# AMP_1_1.net
KiCad netlist of a schematic drawn in EAGLE
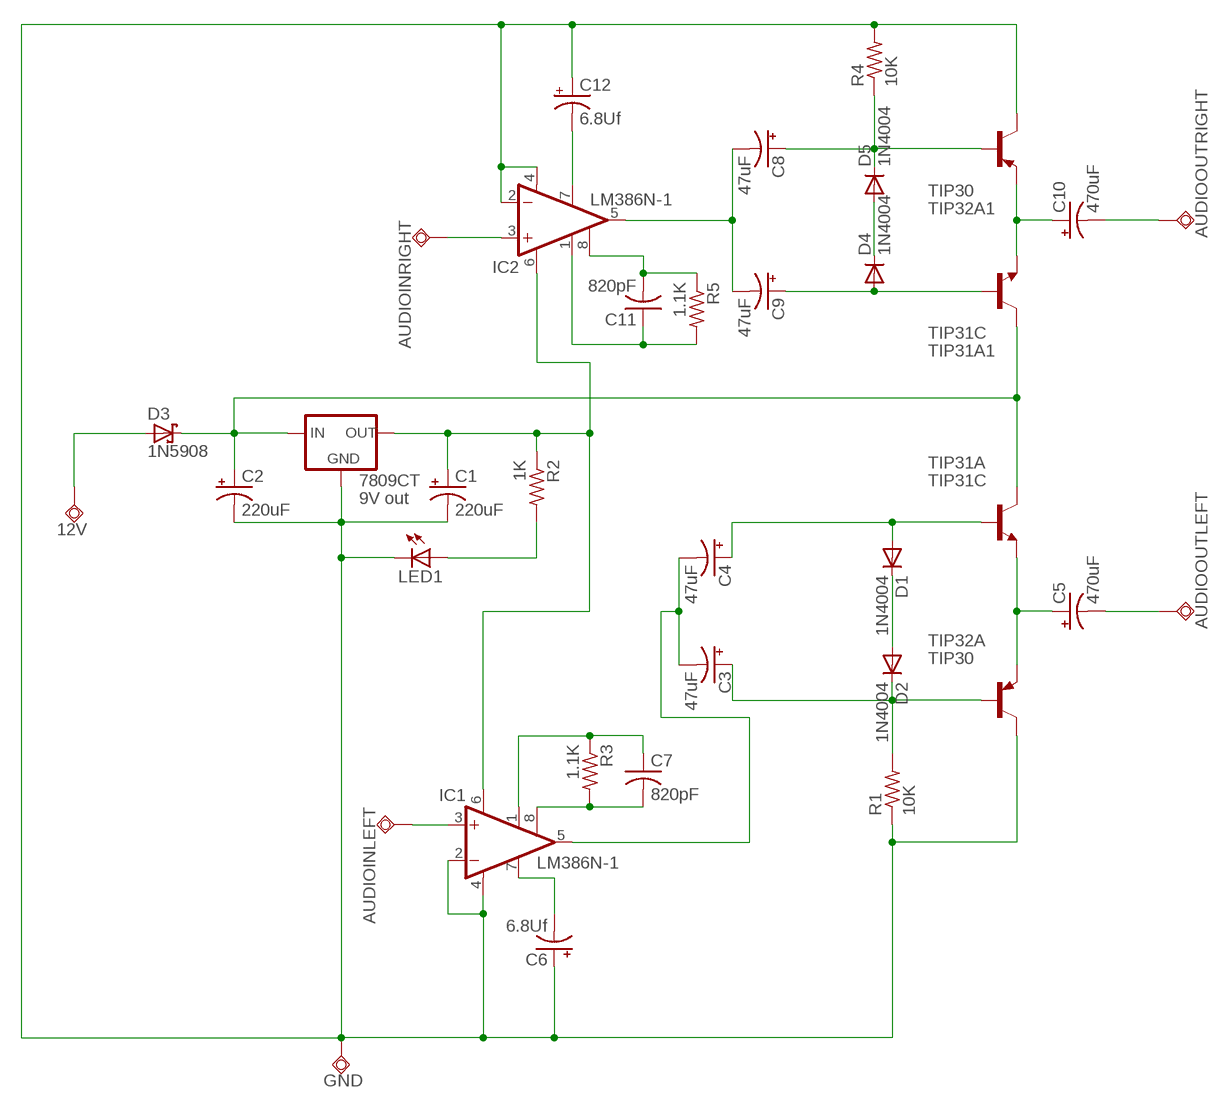
[diagram p0: schematic, sheet 1]

(export (version "E")
  (design (tool "Eeschema 10.0.6"))
  (components
    (comp (ref "12V")
      (value "TPSQPAD1-20")
      (footprint "eagle-import:P1-20")
      (libsource (lib "eagle-import") (part "TPSQPAD1-20"))
    )
    (comp (ref "7809CT")
      (value "9V out")
      (footprint "eagle-import:78XXL")
      (libsource (lib "eagle-import") (part "78XXL"))
    )
    (comp (ref "AUDIOINLEFT")
      (value "TPSQPAD1-20")
      (footprint "eagle-import:P1-20")
      (libsource (lib "eagle-import") (part "TPSQPAD1-20"))
    )
    (comp (ref "AUDIOINRIGHT")
      (value "TPSQPAD1-20")
      (footprint "eagle-import:P1-20")
      (libsource (lib "eagle-import") (part "TPSQPAD1-20"))
    )
    (comp (ref "AUDIOOUTLEFT")
      (value "TPSQPAD1-20")
      (footprint "eagle-import:P1-20")
      (libsource (lib "eagle-import") (part "TPSQPAD1-20"))
    )
    (comp (ref "AUDIOOUTRIGHT")
      (value "TPSQPAD1-20")
      (footprint "eagle-import:P1-20")
      (libsource (lib "eagle-import") (part "TPSQPAD1-20"))
    )
    (comp (ref "C1")
      (value "220uF")
      (footprint "eagle-import:B45181C")
      (libsource (lib "eagle-import") (part "CPOL-USB45181C"))
    )
    (comp (ref "C2")
      (value "220uF")
      (footprint "eagle-import:B45181C")
      (libsource (lib "eagle-import") (part "CPOL-USB45181C"))
    )
    (comp (ref "C3")
      (value "47uF")
      (footprint "eagle-import:E5-4")
      (libsource (lib "eagle-import") (part "CPOL-USE5-4"))
    )
    (comp (ref "C4")
      (value "47uF")
      (footprint "eagle-import:E5-4")
      (libsource (lib "eagle-import") (part "CPOL-USE5-4"))
    )
    (comp (ref "C5")
      (value "470uF")
      (footprint "eagle-import:E5-4")
      (libsource (lib "eagle-import") (part "CPOL-USE5-4"))
    )
    (comp (ref "C6")
      (value "6.8Uf")
      (footprint "eagle-import:E5-4")
      (libsource (lib "eagle-import") (part "CPOL-USE5-4"))
    )
    (comp (ref "C7")
      (value "820pF")
      (footprint "eagle-import:C050-050X075")
      (libsource (lib "eagle-import") (part "C-US050-050X075"))
    )
    (comp (ref "C8")
      (value "47uF")
      (footprint "eagle-import:E5-4")
      (libsource (lib "eagle-import") (part "CPOL-USE5-4"))
    )
    (comp (ref "C9")
      (value "47uF")
      (footprint "eagle-import:E5-4")
      (libsource (lib "eagle-import") (part "CPOL-USE5-4"))
    )
    (comp (ref "C10")
      (value "470uF")
      (footprint "eagle-import:E5-4")
      (libsource (lib "eagle-import") (part "CPOL-USE5-4"))
    )
    (comp (ref "C11")
      (value "820pF")
      (footprint "eagle-import:C050-050X075")
      (libsource (lib "eagle-import") (part "C-US050-050X075"))
    )
    (comp (ref "C12")
      (value "6.8Uf")
      (footprint "eagle-import:E5-4")
      (libsource (lib "eagle-import") (part "CPOL-USE5-4"))
    )
    (comp (ref "D1")
      (value "1N4004")
      (footprint "eagle-import:DO41-10")
      (libsource (lib "eagle-import") (part "1N4004"))
    )
    (comp (ref "D2")
      (value "1N4004")
      (footprint "eagle-import:DO41-10")
      (libsource (lib "eagle-import") (part "1N4004"))
    )
    (comp (ref "D3")
      (value "1N5908")
      (footprint "eagle-import:C4111-15")
      (libsource (lib "eagle-import") (part "1N5908"))
    )
    (comp (ref "D4")
      (value "1N4004")
      (footprint "eagle-import:DO41-10")
      (libsource (lib "eagle-import") (part "1N4004"))
    )
    (comp (ref "D5")
      (value "1N4004")
      (footprint "eagle-import:DO41-10")
      (libsource (lib "eagle-import") (part "1N4004"))
    )
    (comp (ref "GND")
      (value "TPSQPAD1-20")
      (footprint "eagle-import:P1-20")
      (libsource (lib "eagle-import") (part "TPSQPAD1-20"))
    )
    (comp (ref "IC1")
      (value "LM386N-1")
      (footprint "eagle-import:DIL08")
      (libsource (lib "eagle-import") (part "LM386?-N1"))
    )
    (comp (ref "IC2")
      (value "LM386N-1")
      (footprint "eagle-import:DIL08")
      (libsource (lib "eagle-import") (part "LM386?-N1"))
    )
    (comp (ref "LED1")
      (value "LED5MM")
      (footprint "eagle-import:LED5MM")
      (libsource (lib "eagle-import") (part "LED5MM"))
    )
    (comp (ref "R1")
      (value "10K")
      (footprint "eagle-import:0204_7")
      (libsource (lib "eagle-import") (part "R-US_0204/7"))
    )
    (comp (ref "R2")
      (value "1K")
      (footprint "eagle-import:0204_7")
      (libsource (lib "eagle-import") (part "R-US_0204/7"))
    )
    (comp (ref "R3")
      (value "1.1K")
      (footprint "eagle-import:0204_7")
      (libsource (lib "eagle-import") (part "R-US_0204/7"))
    )
    (comp (ref "R4")
      (value "10K")
      (footprint "eagle-import:0204_7")
      (libsource (lib "eagle-import") (part "R-US_0204/7"))
    )
    (comp (ref "R5")
      (value "1.1K")
      (footprint "eagle-import:0204_7")
      (libsource (lib "eagle-import") (part "R-US_0204/7"))
    )
    (comp (ref "TIP31A")
      (value "TIP31C")
      (footprint "eagle-import:TO220")
      (libsource (lib "eagle-import") (part "TIP31C"))
    )
    (comp (ref "TIP31A1")
      (value "TIP31C")
      (footprint "eagle-import:TO220")
      (libsource (lib "eagle-import") (part "TIP31C"))
    )
    (comp (ref "TIP32A")
      (value "TIP30")
      (footprint "eagle-import:TO220")
      (libsource (lib "eagle-import") (part "TIP30"))
    )
    (comp (ref "TIP32A1")
      (value "TIP30")
      (footprint "eagle-import:TO220")
      (libsource (lib "eagle-import") (part "TIP30"))
    )
  )
  (nets
    (net (code "1") (name "Net-(12V-PadTP)") (class "Default")
      (node (ref "12V") (pin "TP") (pinfunction "TP_TP") (pintype "input"))
      (node (ref "D3") (pin "A") (pinfunction "A_A") (pintype "passive"))
    )
    (net (code "2") (name "Net-(AUDIOOUTLEFT-PadTP)") (class "Default")
      (node (ref "AUDIOOUTLEFT") (pin "TP") (pinfunction "TP_TP") (pintype "input"))
      (node (ref "C5") (pin "-") (pinfunction "-_-") (pintype "passive"))
    )
    (net (code "3") (name "Net-(AUDIOOUTRIGHT-PadTP)") (class "Default")
      (node (ref "AUDIOOUTRIGHT") (pin "TP") (pinfunction "TP_TP") (pintype "input"))
      (node (ref "C10") (pin "-") (pinfunction "-_-") (pintype "passive"))
    )
    (net (code "4") (name "Net-(C7-Pad1)") (class "Default")
      (node (ref "C7") (pin "1") (pinfunction "1_1") (pintype "passive"))
      (node (ref "IC1") (pin "1") (pinfunction "GAIN_1") (pintype "passive"))
      (node (ref "R3") (pin "1") (pinfunction "1_1") (pintype "passive"))
    )
    (net (code "5") (name "Net-(C7-Pad2)") (class "Default")
      (node (ref "C7") (pin "2") (pinfunction "2_2") (pintype "passive"))
      (node (ref "IC1") (pin "8") (pinfunction "GAIN_8") (pintype "passive"))
      (node (ref "R3") (pin "2") (pinfunction "2_2") (pintype "passive"))
    )
    (net (code "6") (name "Net-(C11-Pad1)") (class "Default")
      (node (ref "C11") (pin "1") (pinfunction "1_1") (pintype "passive"))
      (node (ref "IC2") (pin "1") (pinfunction "GAIN_1") (pintype "passive"))
      (node (ref "R5") (pin "2") (pinfunction "2_2") (pintype "passive"))
    )
    (net (code "7") (name "Net-(C11-Pad2)") (class "Default")
      (node (ref "C11") (pin "2") (pinfunction "2_2") (pintype "passive"))
      (node (ref "IC2") (pin "8") (pinfunction "GAIN_8") (pintype "passive"))
      (node (ref "R5") (pin "1") (pinfunction "1_1") (pintype "passive"))
    )
    (net (code "8") (name "Net-(D1-PadC)") (class "Default")
      (node (ref "D1") (pin "C") (pinfunction "C_C") (pintype "passive"))
      (node (ref "D2") (pin "A") (pinfunction "A_A") (pintype "passive"))
    )
    (net (code "9") (name "Net-(D4-PadC)") (class "Default")
      (node (ref "D4") (pin "C") (pinfunction "C_C") (pintype "passive"))
      (node (ref "D5") (pin "A") (pinfunction "A_A") (pintype "passive"))
    )
    (net (code "10") (name "Net-(IC1-+IN)") (class "Default")
      (node (ref "AUDIOINLEFT") (pin "TP") (pinfunction "TP_TP") (pintype "input"))
      (node (ref "IC1") (pin "3") (pinfunction "+IN_3") (pintype "input"))
    )
    (net (code "11") (name "Net-(IC1--IN)") (class "Default")
      (node (ref "7809CT") (pin "GND") (pinfunction "GND_GND") (pintype "input"))
      (node (ref "C1") (pin "-") (pinfunction "-_-") (pintype "passive"))
      (node (ref "C12") (pin "+") (pinfunction "+_+") (pintype "passive"))
      (node (ref "C2") (pin "-") (pinfunction "-_-") (pintype "passive"))
      (node (ref "C6") (pin "+") (pinfunction "+_+") (pintype "passive"))
      (node (ref "GND") (pin "TP") (pinfunction "TP_TP") (pintype "input"))
      (node (ref "IC1") (pin "2") (pinfunction "-IN_2") (pintype "input"))
      (node (ref "IC1") (pin "4") (pinfunction "GND_4") (pintype "power_in"))
      (node (ref "IC2") (pin "2") (pinfunction "-IN_2") (pintype "input"))
      (node (ref "IC2") (pin "4") (pinfunction "GND_4") (pintype "power_in"))
      (node (ref "LED1") (pin "K") (pinfunction "C_K") (pintype "passive"))
      (node (ref "R1") (pin "1") (pinfunction "1_1") (pintype "passive"))
      (node (ref "R4") (pin "2") (pinfunction "2_2") (pintype "passive"))
      (node (ref "TIP32A") (pin "2") (pinfunction "C_2") (pintype "passive"))
      (node (ref "TIP32A1") (pin "2") (pinfunction "C_2") (pintype "passive"))
    )
    (net (code "12") (name "Net-(IC1-BYPASS)") (class "Default")
      (node (ref "C6") (pin "-") (pinfunction "-_-") (pintype "passive"))
      (node (ref "IC1") (pin "7") (pinfunction "BYPASS_7") (pintype "passive"))
    )
    (net (code "13") (name "Net-(IC1-OUT)") (class "Default")
      (node (ref "C3") (pin "-") (pinfunction "-_-") (pintype "passive"))
      (node (ref "C4") (pin "-") (pinfunction "-_-") (pintype "passive"))
      (node (ref "IC1") (pin "5") (pinfunction "OUT_5") (pintype "output"))
    )
    (net (code "14") (name "Net-(IC1-VS)") (class "Default")
      (node (ref "7809CT") (pin "OUT") (pinfunction "OUT_OUT") (pintype "passive"))
      (node (ref "C1") (pin "+") (pinfunction "+_+") (pintype "passive"))
      (node (ref "IC1") (pin "6") (pinfunction "VS_6") (pintype "power_in"))
      (node (ref "IC2") (pin "6") (pinfunction "VS_6") (pintype "power_in"))
      (node (ref "R2") (pin "1") (pinfunction "1_1") (pintype "passive"))
    )
    (net (code "15") (name "Net-(IC2-+IN)") (class "Default")
      (node (ref "AUDIOINRIGHT") (pin "TP") (pinfunction "TP_TP") (pintype "input"))
      (node (ref "IC2") (pin "3") (pinfunction "+IN_3") (pintype "input"))
    )
    (net (code "16") (name "Net-(IC2-BYPASS)") (class "Default")
      (node (ref "C12") (pin "-") (pinfunction "-_-") (pintype "passive"))
      (node (ref "IC2") (pin "7") (pinfunction "BYPASS_7") (pintype "passive"))
    )
    (net (code "17") (name "Net-(IC2-OUT)") (class "Default")
      (node (ref "C8") (pin "-") (pinfunction "-_-") (pintype "passive"))
      (node (ref "C9") (pin "-") (pinfunction "-_-") (pintype "passive"))
      (node (ref "IC2") (pin "5") (pinfunction "OUT_5") (pintype "output"))
    )
    (net (code "18") (name "Net-(LED1-PadA)") (class "Default")
      (node (ref "LED1") (pin "A") (pinfunction "A_A") (pintype "passive"))
      (node (ref "R2") (pin "2") (pinfunction "2_2") (pintype "passive"))
    )
    (net (code "19") (name "Net-(TIP31A-B)") (class "Default")
      (node (ref "C4") (pin "+") (pinfunction "+_+") (pintype "passive"))
      (node (ref "D1") (pin "A") (pinfunction "A_A") (pintype "passive"))
      (node (ref "TIP31A") (pin "1") (pinfunction "B_1") (pintype "passive"))
    )
    (net (code "20") (name "Net-(TIP31A-C)") (class "Default")
      (node (ref "7809CT") (pin "IN") (pinfunction "IN_IN") (pintype "input"))
      (node (ref "C2") (pin "+") (pinfunction "+_+") (pintype "passive"))
      (node (ref "D3") (pin "C") (pinfunction "C_C") (pintype "passive"))
      (node (ref "TIP31A") (pin "2") (pinfunction "C_2") (pintype "passive"))
      (node (ref "TIP31A1") (pin "2") (pinfunction "C_2") (pintype "passive"))
    )
    (net (code "21") (name "Net-(TIP31A-E)") (class "Default")
      (node (ref "C5") (pin "+") (pinfunction "+_+") (pintype "passive"))
      (node (ref "TIP31A") (pin "3") (pinfunction "E_3") (pintype "passive"))
      (node (ref "TIP32A") (pin "3") (pinfunction "E_3") (pintype "passive"))
    )
    (net (code "22") (name "Net-(TIP31A1-B)") (class "Default")
      (node (ref "C9") (pin "+") (pinfunction "+_+") (pintype "passive"))
      (node (ref "D4") (pin "A") (pinfunction "A_A") (pintype "passive"))
      (node (ref "TIP31A1") (pin "1") (pinfunction "B_1") (pintype "passive"))
    )
    (net (code "23") (name "Net-(TIP31A1-E)") (class "Default")
      (node (ref "C10") (pin "+") (pinfunction "+_+") (pintype "passive"))
      (node (ref "TIP31A1") (pin "3") (pinfunction "E_3") (pintype "passive"))
      (node (ref "TIP32A1") (pin "3") (pinfunction "E_3") (pintype "passive"))
    )
    (net (code "24") (name "Net-(TIP32A-B)") (class "Default")
      (node (ref "C3") (pin "+") (pinfunction "+_+") (pintype "passive"))
      (node (ref "D2") (pin "C") (pinfunction "C_C") (pintype "passive"))
      (node (ref "R1") (pin "2") (pinfunction "2_2") (pintype "passive"))
      (node (ref "TIP32A") (pin "1") (pinfunction "B_1") (pintype "passive"))
    )
    (net (code "25") (name "Net-(TIP32A1-B)") (class "Default")
      (node (ref "C8") (pin "+") (pinfunction "+_+") (pintype "passive"))
      (node (ref "D5") (pin "C") (pinfunction "C_C") (pintype "passive"))
      (node (ref "R4") (pin "1") (pinfunction "1_1") (pintype "passive"))
      (node (ref "TIP32A1") (pin "1") (pinfunction "B_1") (pintype "passive"))
    )
  )
)
